# main_board.net
KiCad netlist of a schematic drawn in Altium Designer
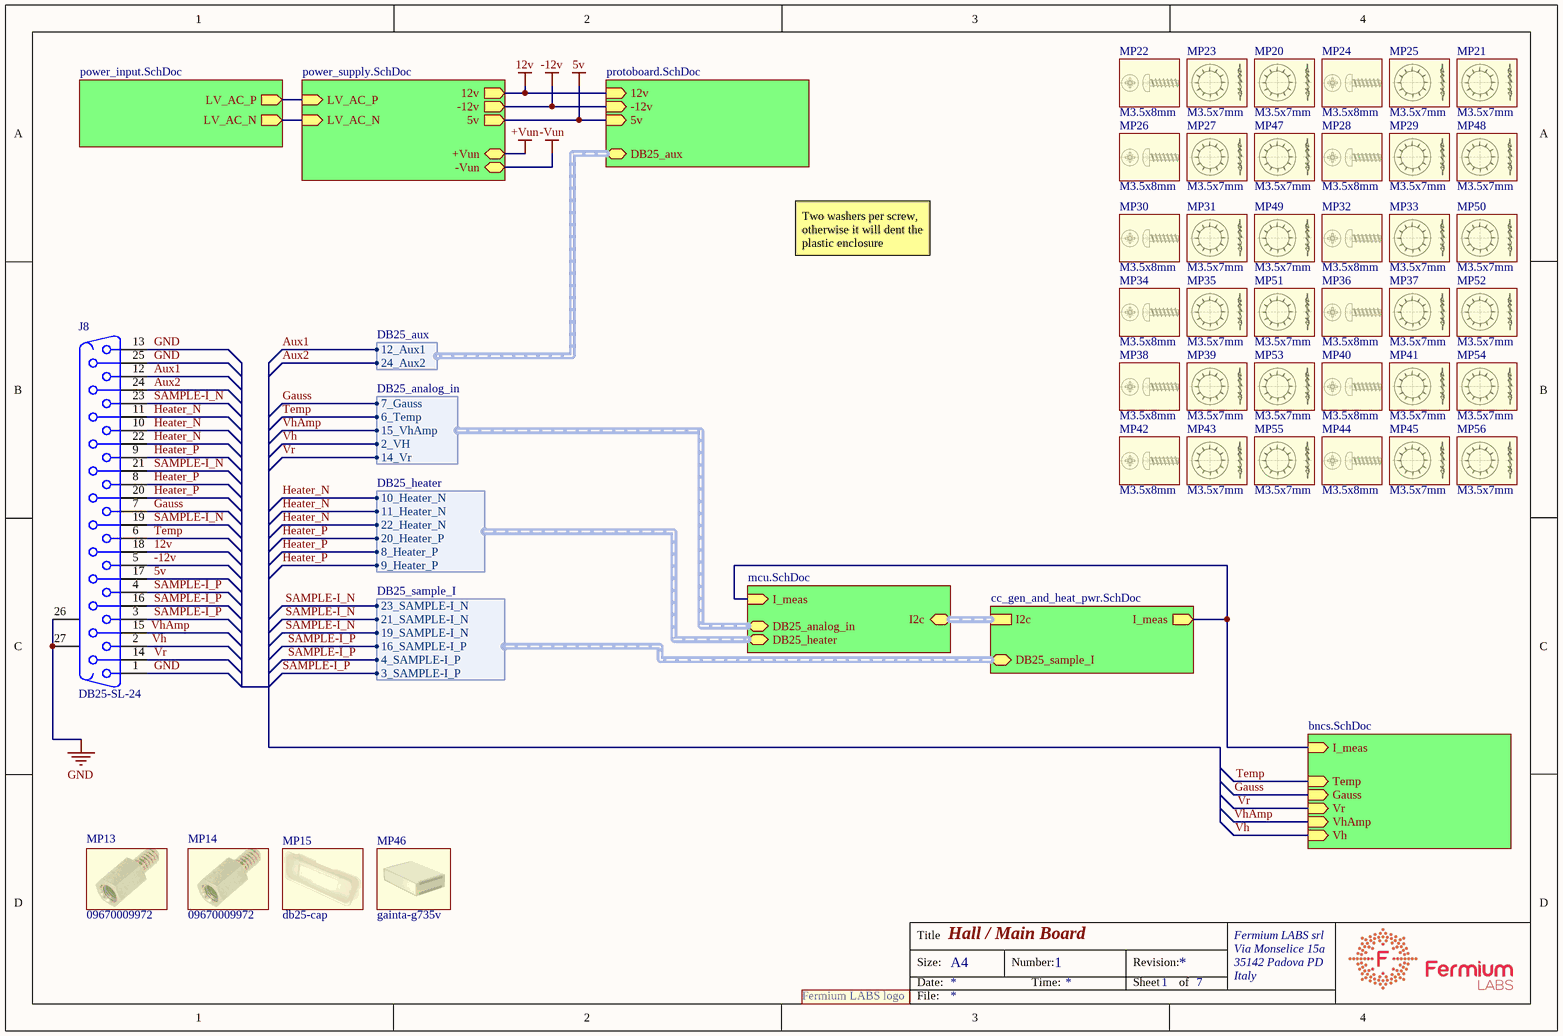
[diagram p0: main_board.SchDoc]

(export (version "E")
  (design (tool "Eeschema 10.0.6"))
  (components
    (comp (ref "J8")
      (value "~")
      (footprint "custom_components:DB25")
      (description "d-sub, 25 pins,  Right Angle")
      (fields
        (field (name "SUPPLIER PART NUMBER 1") "DB25-SL-24")
        (field (name "MANUFACTURER") "ADAM TECH")
        (field (name "MANUFACTURER PART NUMBER") "DB25-SL-24")
      )
      (libsource (lib "Miscellaneous Connectors") (part "D Connector 25"))
    )
    (comp (ref "logo")
      (value "~")
      (footprint "frm-med")
      (libsource (lib "custom_components") (part "fermiumlabs-logo"))
    )
    (comp (ref "MP13")
      (value "09670009972")
      (fields (field (name "MANUFACTURER") "HARTING"))
      (libsource (lib "custom_components") (part "09670009972"))
    )
    (comp (ref "MP14")
      (value "09670009972")
      (fields (field (name "MANUFACTURER") "HARTING"))
      (libsource (lib "custom_components") (part "09670009972"))
    )
    (comp (ref "MP15")
      (value "db25-cap")
      (fields
        (field (name "MANUFACTURER PART NUMBER") "2105-0100-03")
        (field (name "MANUFACTURER") "Encitech")
      )
      (libsource (lib "custom_components") (part "db25-cap"))
    )
    (comp (ref "MP20")
      (value "rondella-dentata-m3.5_1")
      (fields
        (field (name "MANUFACTURER PART NUMBER") "M3.5/BN782 DIN6798J")
        (field (name "MANUFACTURER") "BOSSARD")
        (field (name "SIZE") "M3.5x7mm")
      )
      (libsource (lib "custom_components") (part "rondella-dentata-m3.5_1"))
    )
    (comp (ref "MP21")
      (value "rondella-dentata-m3.5_1")
      (fields
        (field (name "MANUFACTURER PART NUMBER") "M3.5/BN782 DIN6798J")
        (field (name "MANUFACTURER") "BOSSARD")
        (field (name "SIZE") "M3.5x7mm")
      )
      (libsource (lib "custom_components") (part "rondella-dentata-m3.5_1"))
    )
    (comp (ref "MP22")
      (value "screw-3.5x8-plasticc_1")
      (fields
        (field (name "MANUFACTURER PART NUMBER") "M3.5X8/BN82428")
        (field (name "MANUFACTURER") "BOSSARD")
        (field (name "SIZE") "M3.5x8mm")
      )
      (libsource (lib "custom_components") (part "screw-3.5x8-plasticc_1"))
    )
    (comp (ref "MP23")
      (value "rondella-dentata-m3.5_1")
      (fields
        (field (name "MANUFACTURER PART NUMBER") "M3.5/BN782 DIN6798J")
        (field (name "MANUFACTURER") "BOSSARD")
        (field (name "SIZE") "M3.5x7mm")
      )
      (libsource (lib "custom_components") (part "rondella-dentata-m3.5_1"))
    )
    (comp (ref "MP24")
      (value "screw-3.5x8-plasticc_1")
      (fields
        (field (name "MANUFACTURER PART NUMBER") "M3.5X8/BN82428")
        (field (name "MANUFACTURER") "BOSSARD")
        (field (name "SIZE") "M3.5x8mm")
      )
      (libsource (lib "custom_components") (part "screw-3.5x8-plasticc_1"))
    )
    (comp (ref "MP25")
      (value "rondella-dentata-m3.5_1")
      (fields
        (field (name "MANUFACTURER PART NUMBER") "M3.5/BN782 DIN6798J")
        (field (name "MANUFACTURER") "BOSSARD")
        (field (name "SIZE") "M3.5x7mm")
      )
      (libsource (lib "custom_components") (part "rondella-dentata-m3.5_1"))
    )
    (comp (ref "MP26")
      (value "screw-3.5x8-plasticc_1")
      (fields
        (field (name "MANUFACTURER PART NUMBER") "M3.5X8/BN82428")
        (field (name "MANUFACTURER") "BOSSARD")
        (field (name "SIZE") "M3.5x8mm")
      )
      (libsource (lib "custom_components") (part "screw-3.5x8-plasticc_1"))
    )
    (comp (ref "MP27")
      (value "rondella-dentata-m3.5_1")
      (fields
        (field (name "MANUFACTURER PART NUMBER") "M3.5/BN782 DIN6798J")
        (field (name "MANUFACTURER") "BOSSARD")
        (field (name "SIZE") "M3.5x7mm")
      )
      (libsource (lib "custom_components") (part "rondella-dentata-m3.5_1"))
    )
    (comp (ref "MP28")
      (value "screw-3.5x8-plasticc_1")
      (fields
        (field (name "MANUFACTURER PART NUMBER") "M3.5X8/BN82428")
        (field (name "MANUFACTURER") "BOSSARD")
        (field (name "SIZE") "M3.5x8mm")
      )
      (libsource (lib "custom_components") (part "screw-3.5x8-plasticc_1"))
    )
    (comp (ref "MP29")
      (value "rondella-dentata-m3.5_1")
      (fields
        (field (name "MANUFACTURER PART NUMBER") "M3.5/BN782 DIN6798J")
        (field (name "MANUFACTURER") "BOSSARD")
        (field (name "SIZE") "M3.5x7mm")
      )
      (libsource (lib "custom_components") (part "rondella-dentata-m3.5_1"))
    )
    (comp (ref "MP30")
      (value "screw-3.5x8-plasticc_1")
      (fields
        (field (name "MANUFACTURER PART NUMBER") "M3.5X8/BN82428")
        (field (name "MANUFACTURER") "BOSSARD")
        (field (name "SIZE") "M3.5x8mm")
      )
      (libsource (lib "custom_components") (part "screw-3.5x8-plasticc_1"))
    )
    (comp (ref "MP31")
      (value "rondella-dentata-m3.5_1")
      (fields
        (field (name "MANUFACTURER PART NUMBER") "M3.5/BN782 DIN6798J")
        (field (name "MANUFACTURER") "BOSSARD")
        (field (name "SIZE") "M3.5x7mm")
      )
      (libsource (lib "custom_components") (part "rondella-dentata-m3.5_1"))
    )
    (comp (ref "MP32")
      (value "screw-3.5x8-plasticc_1")
      (fields
        (field (name "MANUFACTURER PART NUMBER") "M3.5X8/BN82428")
        (field (name "MANUFACTURER") "BOSSARD")
        (field (name "SIZE") "M3.5x8mm")
      )
      (libsource (lib "custom_components") (part "screw-3.5x8-plasticc_1"))
    )
    (comp (ref "MP33")
      (value "rondella-dentata-m3.5_1")
      (fields
        (field (name "MANUFACTURER PART NUMBER") "M3.5/BN782 DIN6798J")
        (field (name "MANUFACTURER") "BOSSARD")
        (field (name "SIZE") "M3.5x7mm")
      )
      (libsource (lib "custom_components") (part "rondella-dentata-m3.5_1"))
    )
    (comp (ref "MP34")
      (value "screw-3.5x8-plasticc_1")
      (fields
        (field (name "MANUFACTURER PART NUMBER") "M3.5X8/BN82428")
        (field (name "MANUFACTURER") "BOSSARD")
        (field (name "SIZE") "M3.5x8mm")
      )
      (libsource (lib "custom_components") (part "screw-3.5x8-plasticc_1"))
    )
    (comp (ref "MP35")
      (value "rondella-dentata-m3.5_1")
      (fields
        (field (name "MANUFACTURER PART NUMBER") "M3.5/BN782 DIN6798J")
        (field (name "MANUFACTURER") "BOSSARD")
        (field (name "SIZE") "M3.5x7mm")
      )
      (libsource (lib "custom_components") (part "rondella-dentata-m3.5_1"))
    )
    (comp (ref "MP36")
      (value "screw-3.5x8-plasticc_1")
      (fields
        (field (name "MANUFACTURER PART NUMBER") "M3.5X8/BN82428")
        (field (name "MANUFACTURER") "BOSSARD")
        (field (name "SIZE") "M3.5x8mm")
      )
      (libsource (lib "custom_components") (part "screw-3.5x8-plasticc_1"))
    )
    (comp (ref "MP37")
      (value "rondella-dentata-m3.5_1")
      (fields
        (field (name "MANUFACTURER PART NUMBER") "M3.5/BN782 DIN6798J")
        (field (name "MANUFACTURER") "BOSSARD")
        (field (name "SIZE") "M3.5x7mm")
      )
      (libsource (lib "custom_components") (part "rondella-dentata-m3.5_1"))
    )
    (comp (ref "MP38")
      (value "screw-3.5x8-plasticc_1")
      (fields
        (field (name "MANUFACTURER PART NUMBER") "M3.5X8/BN82428")
        (field (name "MANUFACTURER") "BOSSARD")
        (field (name "SIZE") "M3.5x8mm")
      )
      (libsource (lib "custom_components") (part "screw-3.5x8-plasticc_1"))
    )
    (comp (ref "MP39")
      (value "rondella-dentata-m3.5_1")
      (fields
        (field (name "MANUFACTURER PART NUMBER") "M3.5/BN782 DIN6798J")
        (field (name "MANUFACTURER") "BOSSARD")
        (field (name "SIZE") "M3.5x7mm")
      )
      (libsource (lib "custom_components") (part "rondella-dentata-m3.5_1"))
    )
    (comp (ref "MP40")
      (value "screw-3.5x8-plasticc_1")
      (fields
        (field (name "MANUFACTURER PART NUMBER") "M3.5X8/BN82428")
        (field (name "MANUFACTURER") "BOSSARD")
        (field (name "SIZE") "M3.5x8mm")
      )
      (libsource (lib "custom_components") (part "screw-3.5x8-plasticc_1"))
    )
    (comp (ref "MP41")
      (value "rondella-dentata-m3.5_1")
      (fields
        (field (name "MANUFACTURER PART NUMBER") "M3.5/BN782 DIN6798J")
        (field (name "MANUFACTURER") "BOSSARD")
        (field (name "SIZE") "M3.5x7mm")
      )
      (libsource (lib "custom_components") (part "rondella-dentata-m3.5_1"))
    )
    (comp (ref "MP42")
      (value "screw-3.5x8-plasticc_1")
      (fields
        (field (name "MANUFACTURER PART NUMBER") "M3.5X8/BN82428")
        (field (name "MANUFACTURER") "BOSSARD")
        (field (name "SIZE") "M3.5x8mm")
      )
      (libsource (lib "custom_components") (part "screw-3.5x8-plasticc_1"))
    )
    (comp (ref "MP43")
      (value "rondella-dentata-m3.5_1")
      (fields
        (field (name "MANUFACTURER PART NUMBER") "M3.5/BN782 DIN6798J")
        (field (name "MANUFACTURER") "BOSSARD")
        (field (name "SIZE") "M3.5x7mm")
      )
      (libsource (lib "custom_components") (part "rondella-dentata-m3.5_1"))
    )
    (comp (ref "MP44")
      (value "screw-3.5x8-plasticc_1")
      (fields
        (field (name "MANUFACTURER PART NUMBER") "M3.5X8/BN82428")
        (field (name "MANUFACTURER") "BOSSARD")
        (field (name "SIZE") "M3.5x8mm")
      )
      (libsource (lib "custom_components") (part "screw-3.5x8-plasticc_1"))
    )
    (comp (ref "MP45")
      (value "rondella-dentata-m3.5_1")
      (fields
        (field (name "MANUFACTURER PART NUMBER") "M3.5/BN782 DIN6798J")
        (field (name "MANUFACTURER") "BOSSARD")
        (field (name "SIZE") "M3.5x7mm")
      )
      (libsource (lib "custom_components") (part "rondella-dentata-m3.5_1"))
    )
    (comp (ref "MP46")
      (value "gainta-g735v")
      (fields (field (name "MANUFACTURER PART NUMBER") "G735V") (field (name "MANUFACTURER") "GAINTA"))
      (libsource (lib "custom_components") (part "gainta-g735v"))
    )
    (comp (ref "MP47")
      (value "rondella-dentata-m3.5_1")
      (fields
        (field (name "MANUFACTURER PART NUMBER") "M3.5/BN782 DIN6798J")
        (field (name "MANUFACTURER") "BOSSARD")
        (field (name "SIZE") "M3.5x7mm")
      )
      (libsource (lib "custom_components") (part "rondella-dentata-m3.5_1"))
    )
    (comp (ref "MP48")
      (value "rondella-dentata-m3.5_1")
      (fields
        (field (name "MANUFACTURER PART NUMBER") "M3.5/BN782 DIN6798J")
        (field (name "MANUFACTURER") "BOSSARD")
        (field (name "SIZE") "M3.5x7mm")
      )
      (libsource (lib "custom_components") (part "rondella-dentata-m3.5_1"))
    )
    (comp (ref "MP49")
      (value "rondella-dentata-m3.5_1")
      (fields
        (field (name "MANUFACTURER PART NUMBER") "M3.5/BN782 DIN6798J")
        (field (name "MANUFACTURER") "BOSSARD")
        (field (name "SIZE") "M3.5x7mm")
      )
      (libsource (lib "custom_components") (part "rondella-dentata-m3.5_1"))
    )
    (comp (ref "MP50")
      (value "rondella-dentata-m3.5_1")
      (fields
        (field (name "MANUFACTURER PART NUMBER") "M3.5/BN782 DIN6798J")
        (field (name "MANUFACTURER") "BOSSARD")
        (field (name "SIZE") "M3.5x7mm")
      )
      (libsource (lib "custom_components") (part "rondella-dentata-m3.5_1"))
    )
    (comp (ref "MP51")
      (value "rondella-dentata-m3.5_1")
      (fields
        (field (name "MANUFACTURER PART NUMBER") "M3.5/BN782 DIN6798J")
        (field (name "MANUFACTURER") "BOSSARD")
        (field (name "SIZE") "M3.5x7mm")
      )
      (libsource (lib "custom_components") (part "rondella-dentata-m3.5_1"))
    )
    (comp (ref "MP52")
      (value "rondella-dentata-m3.5_1")
      (fields
        (field (name "MANUFACTURER PART NUMBER") "M3.5/BN782 DIN6798J")
        (field (name "MANUFACTURER") "BOSSARD")
        (field (name "SIZE") "M3.5x7mm")
      )
      (libsource (lib "custom_components") (part "rondella-dentata-m3.5_1"))
    )
    (comp (ref "MP53")
      (value "rondella-dentata-m3.5_1")
      (fields
        (field (name "MANUFACTURER PART NUMBER") "M3.5/BN782 DIN6798J")
        (field (name "MANUFACTURER") "BOSSARD")
        (field (name "SIZE") "M3.5x7mm")
      )
      (libsource (lib "custom_components") (part "rondella-dentata-m3.5_1"))
    )
    (comp (ref "MP54")
      (value "rondella-dentata-m3.5_1")
      (fields
        (field (name "MANUFACTURER PART NUMBER") "M3.5/BN782 DIN6798J")
        (field (name "MANUFACTURER") "BOSSARD")
        (field (name "SIZE") "M3.5x7mm")
      )
      (libsource (lib "custom_components") (part "rondella-dentata-m3.5_1"))
    )
    (comp (ref "MP55")
      (value "rondella-dentata-m3.5_1")
      (fields
        (field (name "MANUFACTURER PART NUMBER") "M3.5/BN782 DIN6798J")
        (field (name "MANUFACTURER") "BOSSARD")
        (field (name "SIZE") "M3.5x7mm")
      )
      (libsource (lib "custom_components") (part "rondella-dentata-m3.5_1"))
    )
    (comp (ref "MP56")
      (value "rondella-dentata-m3.5_1")
      (fields
        (field (name "MANUFACTURER PART NUMBER") "M3.5/BN782 DIN6798J")
        (field (name "MANUFACTURER") "BOSSARD")
        (field (name "SIZE") "M3.5x7mm")
      )
      (libsource (lib "custom_components") (part "rondella-dentata-m3.5_1"))
    )
  )
  (nets
    (net (code "6") (name "-12v") (class "Default")
      (node (ref "J8") (pin "5") (pinfunction "5_5") (pintype "passive"))
    )
    (net (code "8") (name "/Aux1") (class "Default")
      (node (ref "J8") (pin "12") (pinfunction "12_12") (pintype "passive"))
    )
    (net (code "9") (name "/Aux2") (class "Default")
      (node (ref "J8") (pin "24") (pinfunction "24_24") (pintype "passive"))
    )
    (net (code "10") (name "/Gauss") (class "Default")
      (node (ref "J8") (pin "7") (pinfunction "7_7") (pintype "passive"))
    )
    (net (code "11") (name "/Heater_N") (class "Default")
      (node (ref "J8") (pin "10") (pinfunction "10_10") (pintype "passive"))
      (node (ref "J8") (pin "11") (pinfunction "11_11") (pintype "passive"))
      (node (ref "J8") (pin "22") (pinfunction "22_22") (pintype "passive"))
    )
    (net (code "12") (name "/Heater_P") (class "Default")
      (node (ref "J8") (pin "20") (pinfunction "20_20") (pintype "passive"))
      (node (ref "J8") (pin "8") (pinfunction "8_8") (pintype "passive"))
      (node (ref "J8") (pin "9") (pinfunction "9_9") (pintype "passive"))
    )
    (net (code "17") (name "/SAMPLE-I_N") (class "Default")
      (node (ref "J8") (pin "19") (pinfunction "19_19") (pintype "passive"))
      (node (ref "J8") (pin "21") (pinfunction "21_21") (pintype "passive"))
      (node (ref "J8") (pin "23") (pinfunction "23_23") (pintype "passive"))
    )
    (net (code "18") (name "/SAMPLE-I_P") (class "Default")
      (node (ref "J8") (pin "16") (pinfunction "16_16") (pintype "passive"))
      (node (ref "J8") (pin "3") (pinfunction "3_3") (pintype "passive"))
      (node (ref "J8") (pin "4") (pinfunction "4_4") (pintype "passive"))
    )
    (net (code "19") (name "/Temp") (class "Default")
      (node (ref "J8") (pin "6") (pinfunction "6_6") (pintype "passive"))
    )
    (net (code "20") (name "/Vh") (class "Default")
      (node (ref "J8") (pin "2") (pinfunction "2_2") (pintype "passive"))
    )
    (net (code "21") (name "/VhAmp") (class "Default")
      (node (ref "J8") (pin "15") (pinfunction "15_15") (pintype "passive"))
    )
    (net (code "22") (name "/Vr") (class "Default")
      (node (ref "J8") (pin "14") (pinfunction "14_14") (pintype "passive"))
    )
    (net (code "27") (name "5v") (class "Default")
      (node (ref "J8") (pin "17") (pinfunction "17_17") (pintype "passive"))
    )
    (net (code "28") (name "12v") (class "Default")
      (node (ref "J8") (pin "18") (pinfunction "18_18") (pintype "passive"))
    )
    (net (code "29") (name "GND") (class "Default")
      (node (ref "J8") (pin "1") (pinfunction "1_1") (pintype "passive"))
      (node (ref "J8") (pin "13") (pinfunction "13_13") (pintype "passive"))
      (node (ref "J8") (pin "25") (pinfunction "25_25") (pintype "passive"))
      (node (ref "J8") (pin "26") (pinfunction "MH1_26") (pintype "passive"))
      (node (ref "J8") (pin "27") (pinfunction "MH2_27") (pintype "passive"))
    )
  )
)
